# USB_Downloader.net
KiCad netlist of a schematic drawn in Altium Designer
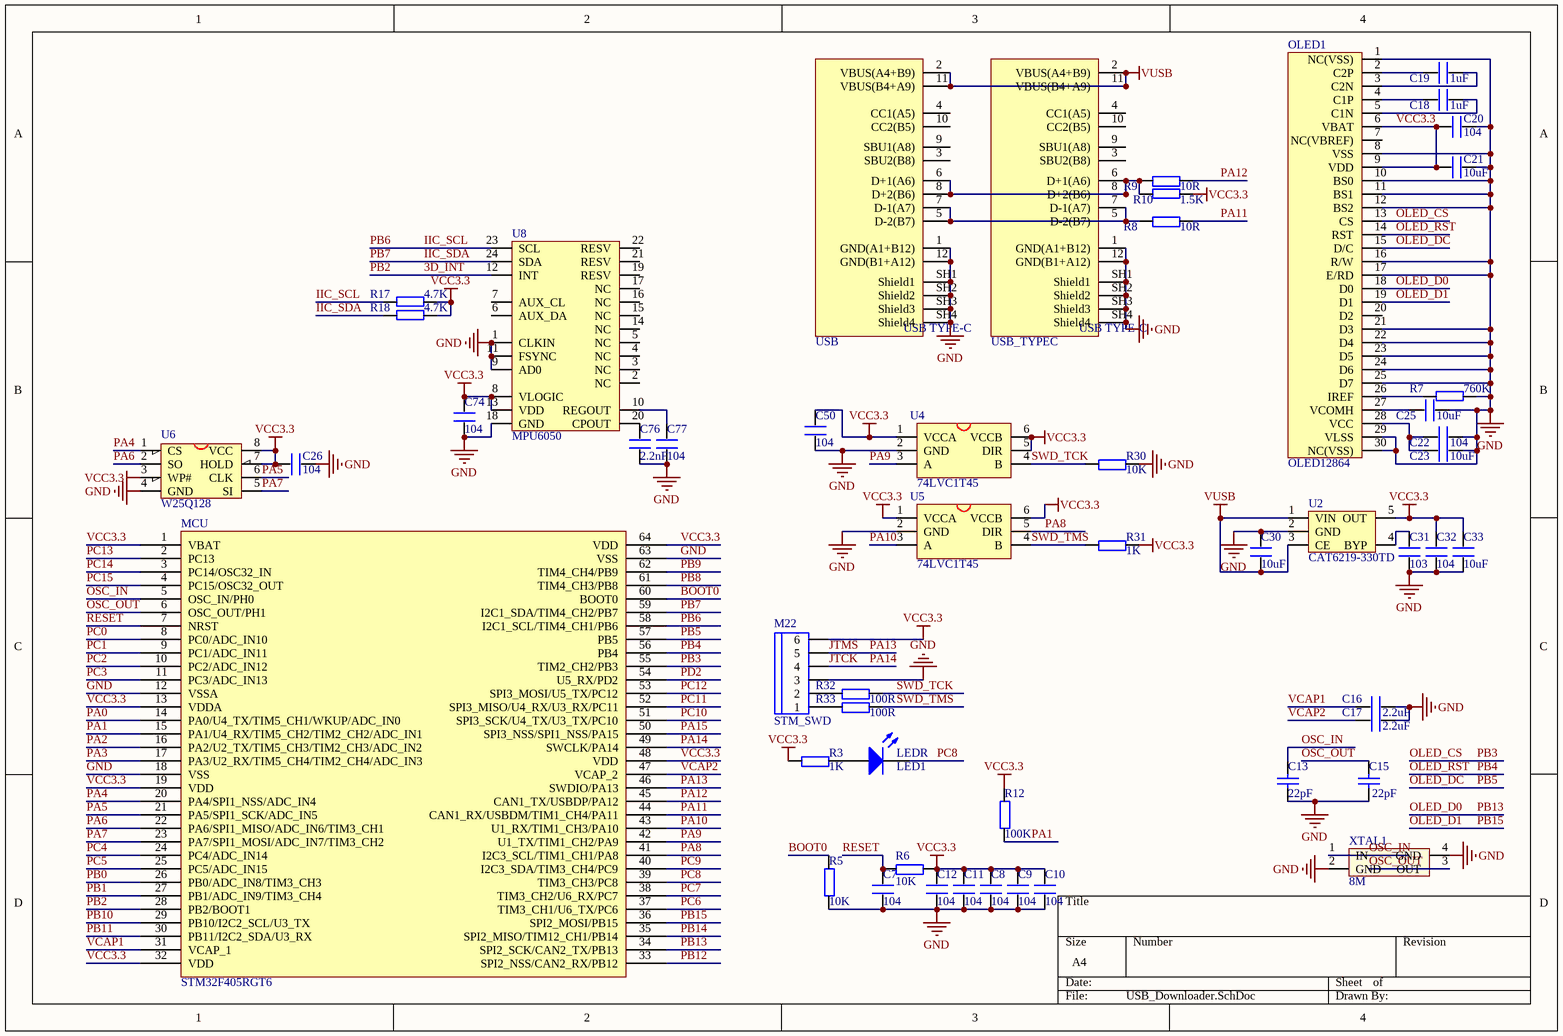
[diagram p0: USB_Downloader.SchDoc]

(export (version "E")
  (design (tool "Eeschema 10.0.6"))
  (components
    (comp (ref "C7")
      (value "104")
      (footprint "C 0603_L")
      (libsource (lib "WarShip V3 STM32103封装库") (part "C"))
    )
    (comp (ref "C8")
      (value "104")
      (footprint "C 0603_L")
      (libsource (lib "WarShip V3 STM32103封装库") (part "C"))
    )
    (comp (ref "C9")
      (value "104")
      (footprint "C 0603_L")
      (libsource (lib "WarShip V3 STM32103封装库") (part "C"))
    )
    (comp (ref "C10")
      (value "104")
      (footprint "C 0603_L")
      (libsource (lib "WarShip V3 STM32103封装库") (part "C"))
    )
    (comp (ref "C11")
      (value "104")
      (footprint "C 0603_L")
      (libsource (lib "WarShip V3 STM32103封装库") (part "C"))
    )
    (comp (ref "C12")
      (value "104")
      (footprint "C 0603_L")
      (libsource (lib "WarShip V3 STM32103封装库") (part "C"))
    )
    (comp (ref "C13") (value "22pF") (footprint "C 0603_L") (libsource (lib "L476") (part "CAP")))
    (comp (ref "C15") (value "22pF") (footprint "C 0603_L") (libsource (lib "L476") (part "CAP")))
    (comp (ref "C16")
      (value "2.2uF")
      (footprint "C 0603_L")
      (libsource (lib "WarShip V3 STM32103封装库") (part "C"))
    )
    (comp (ref "C17")
      (value "2.2uF")
      (footprint "C 0603_L")
      (libsource (lib "WarShip V3 STM32103封装库") (part "C"))
    )
    (comp (ref "C18")
      (value "1uF")
      (footprint "C 0603_L")
      (libsource (lib "WarShip V3 STM32103封装库") (part "C"))
    )
    (comp (ref "C19")
      (value "1uF")
      (footprint "C 0603_L")
      (libsource (lib "WarShip V3 STM32103封装库") (part "C"))
    )
    (comp (ref "C20")
      (value "104")
      (footprint "C 0603_L")
      (libsource (lib "WarShip V3 STM32103封装库") (part "C"))
    )
    (comp (ref "C21")
      (value "10uF")
      (footprint "C 0603_L")
      (libsource (lib "WarShip V3 STM32103封装库") (part "C"))
    )
    (comp (ref "C22")
      (value "104")
      (footprint "C 0603_L")
      (libsource (lib "WarShip V3 STM32103封装库") (part "C"))
    )
    (comp (ref "C23")
      (value "10uF")
      (footprint "C 0603_L")
      (libsource (lib "WarShip V3 STM32103封装库") (part "C"))
    )
    (comp (ref "C25")
      (value "10uF")
      (footprint "C 0603_L")
      (libsource (lib "WarShip V3 STM32103封装库") (part "C"))
    )
    (comp (ref "C26")
      (value "104")
      (footprint "C 0603_L")
      (libsource (lib "WarShip V3 STM32103封装库") (part "C"))
    )
    (comp (ref "C30")
      (value "10uF")
      (footprint "C 0603_L")
      (libsource (lib "WarShip V3 STM32103封装库") (part "C"))
    )
    (comp (ref "C31")
      (value "103")
      (footprint "C 0603_L")
      (libsource (lib "WarShip V3 STM32103封装库") (part "C"))
    )
    (comp (ref "C32")
      (value "104")
      (footprint "C 0603_L")
      (libsource (lib "WarShip V3 STM32103封装库") (part "C"))
    )
    (comp (ref "C33")
      (value "10uF")
      (footprint "C 0603_L")
      (libsource (lib "WarShip V3 STM32103封装库") (part "C"))
    )
    (comp (ref "C50")
      (value "104")
      (footprint "C 0603_L")
      (libsource (lib "WarShip V3 STM32103封装库") (part "C"))
    )
    (comp (ref "C74") (value "104") (footprint "C 0603_L") (libsource (lib "MYCOMLIB") (part "C")))
    (comp (ref "C76") (value "2.2nF") (footprint "C 0603_L") (libsource (lib "MYCOMLIB") (part "C")))
    (comp (ref "C77") (value "104") (footprint "C 0603_L") (libsource (lib "MYCOMLIB") (part "C")))
    (comp (ref "LEDR")
      (value "LED1")
      (footprint "LED 0805B")
      (description "Typical RED, GREEN, YELLOW, AMBER GaAs LED")
      (fields (field (name "PUBLISHER") "Altium Limited"))
      (libsource (lib "阿波罗STM32F4&F7底板封装库") (part "LED2"))
    )
    (comp (ref "M22") (value "STM_SWD") (footprint "SH1.0-6P") (libsource (lib "MiniFly ") (part "HEAD6")))
    (comp (ref "MCU")
      (value "STM32F405RGT6")
      (footprint "LQFP64 10X10_L")
      (description "Flaah:256/RAM:48/IO:51")
      (libsource (lib "ATKF405 V1.1") (part "STM32F405RGT6"))
    )
    (comp (ref "OLED1")
      (value "OLED12864")
      (footprint "OLED_0.96")
      (libsource (lib "OLED模块封装库") (part "OLED12864"))
    )
    (comp (ref "R3")
      (value "1K")
      (footprint "R 0603_L")
      (libsource (lib "WarShip V3 STM32103封装库") (part "R"))
    )
    (comp (ref "R5")
      (value "10K")
      (footprint "R 0603_L")
      (libsource (lib "WarShip V3 STM32103封装库") (part "R"))
    )
    (comp (ref "R6")
      (value "10K")
      (footprint "R 0603_L")
      (libsource (lib "WarShip V3 STM32103封装库") (part "R"))
    )
    (comp (ref "R7")
      (value "760K")
      (footprint "R 0603_L")
      (libsource (lib "WarShip V3 STM32103封装库") (part "R"))
    )
    (comp (ref "R8")
      (value "10R")
      (footprint "R 0603_L")
      (libsource (lib "WarShip V3 STM32103封装库") (part "R"))
    )
    (comp (ref "R9")
      (value "10R")
      (footprint "R 0603_L")
      (libsource (lib "WarShip V3 STM32103封装库") (part "R"))
    )
    (comp (ref "R10")
      (value "1.5K")
      (footprint "R 0603_L")
      (libsource (lib "WarShip V3 STM32103封装库") (part "R"))
    )
    (comp (ref "R12")
      (value "100K")
      (footprint "R 0603_L")
      (libsource (lib "WarShip V3 STM32103封装库") (part "R"))
    )
    (comp (ref "R17")
      (value "4.7K")
      (footprint "R 0603_L")
      (libsource (lib "WarShip V3 STM32103封装库") (part "R"))
    )
    (comp (ref "R18")
      (value "4.7K")
      (footprint "R 0603_L")
      (libsource (lib "WarShip V3 STM32103封装库") (part "R"))
    )
    (comp (ref "R30")
      (value "10K")
      (footprint "R 0603_L")
      (libsource (lib "WarShip V3 STM32103封装库") (part "R"))
    )
    (comp (ref "R31")
      (value "1K")
      (footprint "R 0603_L")
      (libsource (lib "WarShip V3 STM32103封装库") (part "R"))
    )
    (comp (ref "R32")
      (value "100R")
      (footprint "R 0603_L")
      (libsource (lib "WarShip V3 STM32103封装库") (part "R"))
    )
    (comp (ref "R33")
      (value "100R")
      (footprint "R 0603_L")
      (libsource (lib "WarShip V3 STM32103封装库") (part "R"))
    )
    (comp (ref "U2")
      (value "CAT6219-330TD")
      (footprint "SOT23-5L")
      (description "3.3V 500mA LDO")
      (libsource (lib "STM32H743核心板封装库") (part "CAT6219-330TD"))
    )
    (comp (ref "U4")
      (value "74LVC1T45")
      (footprint "SOT363-6L")
      (description "1路双向电平转换")
      (libsource (lib "LovelessingSch") (part "74LVC1T45"))
    )
    (comp (ref "U5")
      (value "74LVC1T45")
      (footprint "SOT363-6L")
      (description "1路双向电平转换")
      (libsource (lib "LovelessingSch") (part "74LVC1T45"))
    )
    (comp (ref "U6")
      (value "W25Q128")
      (footprint "SOP8W_L")
      (description "W25X16;SST25VF016;MX25L1605")
      (libsource (lib "WarShip V3 STM32103封装库") (part "W25X16"))
    )
    (comp (ref "U8")
      (value "MPU6050")
      (footprint "QFN24 4x4_N")
      (description "9轴运动处理传感器")
      (libsource (lib "ALIENTEK_COMPONENT") (part "MPU6050"))
    )
    (comp (ref "USB")
      (value "USB TypeC")
      (footprint "USB Type-C")
      (description "12P TypeC 母座")
      (libsource (lib "ESP32_Weather") (part "USB Type-C"))
    )
    (comp (ref "USB_TYPEC")
      (value "USB TypeC")
      (footprint "USB Type-C")
      (description "12P TypeC 母座")
      (libsource (lib "ESP32_Weather") (part "USB Type-C"))
    )
    (comp (ref "XTAL1")
      (value "8M")
      (footprint "XTAL3225   无源")
      (description "无源贴片晶振")
      (libsource (lib "REMOTOR") (part "XTAL-无源贴片"))
    )
  )
  (nets
    (net (code "1") (name "/3D_INT") (class "Default")
      (node (ref "MCU") (pin "28") (pinfunction "PB2/BOOT1_28") (pintype "passive"))
      (node (ref "U8") (pin "12") (pinfunction "INT_12") (pintype "passive"))
    )
    (net (code "2") (name "/BOOT0") (class "Default")
      (node (ref "MCU") (pin "60") (pinfunction "BOOT0_60") (pintype "passive"))
      (node (ref "R5") (pin "2") (pintype "passive"))
    )
    (net (code "3") (name "/IIC_SCL") (class "Default")
      (node (ref "MCU") (pin "58") (pinfunction "I2C1_SCL/TIM4_CH1/PB6_58") (pintype "passive"))
      (node (ref "R17") (pin "2") (pintype "passive"))
      (node (ref "U8") (pin "23") (pinfunction "SCL_23") (pintype "passive"))
    )
    (net (code "4") (name "/IIC_SDA") (class "Default")
      (node (ref "MCU") (pin "59") (pinfunction "I2C1_SDA/TIM4_CH2/PB7_59") (pintype "passive"))
      (node (ref "R18") (pin "2") (pintype "passive"))
      (node (ref "U8") (pin "24") (pinfunction "SDA_24") (pintype "passive"))
    )
    (net (code "5") (name "/JTCK") (class "Default")
      (node (ref "M22") (pin "4") (pinfunction "4_4") (pintype "passive"))
      (node (ref "MCU") (pin "49") (pinfunction "SWCLK/PA14_49") (pintype "passive"))
    )
    (net (code "6") (name "/JTMS") (class "Default")
      (node (ref "M22") (pin "5") (pinfunction "5_5") (pintype "passive"))
      (node (ref "MCU") (pin "46") (pinfunction "SWDIO/PA13_46") (pintype "passive"))
    )
    (net (code "7") (name "/OLED_CS") (class "Default")
      (node (ref "MCU") (pin "55") (pinfunction "TIM2_CH2/PB3_55") (pintype "passive"))
      (node (ref "OLED1") (pin "13") (pinfunction "CS_13") (pintype "passive"))
    )
    (net (code "8") (name "/OLED_D0") (class "Default")
      (node (ref "MCU") (pin "34") (pinfunction "SPI2_SCK/CAN2_TX/PB13_34") (pintype "passive"))
      (node (ref "OLED1") (pin "18") (pinfunction "D0_18") (pintype "passive"))
    )
    (net (code "9") (name "/OLED_D1") (class "Default")
      (node (ref "MCU") (pin "36") (pinfunction "SPI2_MOSI/PB15_36") (pintype "passive"))
      (node (ref "OLED1") (pin "19") (pinfunction "D1_19") (pintype "passive"))
    )
    (net (code "10") (name "/OLED_DC") (class "Default")
      (node (ref "MCU") (pin "57") (pinfunction "PB5_57") (pintype "passive"))
      (node (ref "OLED1") (pin "15") (pinfunction "D/C_15") (pintype "passive"))
    )
    (net (code "11") (name "/OLED_RST") (class "Default")
      (node (ref "MCU") (pin "56") (pinfunction "PB4_56") (pintype "passive"))
      (node (ref "OLED1") (pin "14") (pinfunction "RST_14") (pintype "passive"))
    )
    (net (code "12") (name "/OSC_IN") (class "Default")
      (node (ref "C13") (pin "2") (pinfunction "2_2") (pintype "passive"))
      (node (ref "MCU") (pin "5") (pinfunction "OSC_IN/PH0_5") (pintype "passive"))
      (node (ref "XTAL1") (pin "1") (pinfunction "IN_1") (pintype "passive"))
    )
    (net (code "13") (name "/OSC_OUT") (class "Default")
      (node (ref "C15") (pin "2") (pinfunction "2_2") (pintype "passive"))
      (node (ref "MCU") (pin "6") (pinfunction "OSC_OUT/PH1_6") (pintype "passive"))
      (node (ref "XTAL1") (pin "3") (pinfunction "OUT_3") (pintype "passive"))
    )
    (net (code "14") (name "/PA0") (class "Default")
      (node (ref "MCU") (pin "14") (pinfunction "PA0/U4_TX/TIM5_CH1/WKUP/ADC_IN0_14") (pintype "passive"))
    )
    (net (code "15") (name "/PA1") (class "Default")
      (node (ref "MCU") (pin "15") (pinfunction "PA1/U4_RX/TIM5_CH2/TIM2_CH2/ADC_IN1_15") (pintype "passive"))
      (node (ref "R12") (pin "1") (pintype "passive"))
    )
    (net (code "16") (name "/PA2") (class "Default")
      (node (ref "MCU") (pin "16") (pinfunction "PA2/U2_TX/TIM5_CH3/TIM2_CH3/ADC_IN2_16") (pintype "passive"))
    )
    (net (code "17") (name "/PA3") (class "Default")
      (node (ref "MCU") (pin "17") (pinfunction "PA3/U2_RX/TIM5_CH4/TIM2_CH4/ADC_IN3_17") (pintype "passive"))
    )
    (net (code "18") (name "/PA4") (class "Default")
      (node (ref "MCU") (pin "20") (pinfunction "PA4/SPI1_NSS/ADC_IN4_20") (pintype "passive"))
      (node (ref "U6") (pin "1") (pinfunction "CS_1") (pintype "passive"))
    )
    (net (code "19") (name "/PA5") (class "Default")
      (node (ref "MCU") (pin "21") (pinfunction "PA5/SPI1_SCK/ADC_IN5_21") (pintype "passive"))
      (node (ref "U6") (pin "6") (pinfunction "CLK_6") (pintype "passive"))
    )
    (net (code "20") (name "/PA6") (class "Default")
      (node (ref "MCU") (pin "22") (pinfunction "PA6/SPI1_MISO/ADC_IN6/TIM3_CH1_22") (pintype "passive"))
      (node (ref "U6") (pin "2") (pinfunction "SO_2") (pintype "passive"))
    )
    (net (code "21") (name "/PA7") (class "Default")
      (node (ref "MCU") (pin "23") (pinfunction "PA7/SPI1_MOSI/ADC_IN7/TIM3_CH2_23") (pintype "passive"))
      (node (ref "U6") (pin "5") (pinfunction "SI_5") (pintype "passive"))
    )
    (net (code "22") (name "/PA8") (class "Default")
      (node (ref "MCU") (pin "41") (pinfunction "I2C3_SCL/TIM1_CH1/PA8_41") (pintype "passive"))
      (node (ref "U5") (pin "5") (pinfunction "DIR_5") (pintype "passive"))
    )
    (net (code "23") (name "/PA9") (class "Default")
      (node (ref "MCU") (pin "42") (pinfunction "U1_TX/TIM1_CH2/PA9_42") (pintype "passive"))
      (node (ref "U4") (pin "3") (pinfunction "A_3") (pintype "passive"))
    )
    (net (code "24") (name "/PA10") (class "Default")
      (node (ref "MCU") (pin "43") (pinfunction "U1_RX/TIM1_CH3/PA10_43") (pintype "passive"))
      (node (ref "U5") (pin "3") (pinfunction "A_3") (pintype "passive"))
    )
    (net (code "25") (name "/PA11") (class "Default")
      (node (ref "MCU") (pin "44") (pinfunction "CAN1_RX/USBDM/TIM1_CH4/PA11_44") (pintype "passive"))
      (node (ref "R8") (pin "2") (pintype "passive"))
    )
    (net (code "26") (name "/PA12") (class "Default")
      (node (ref "MCU") (pin "45") (pinfunction "CAN1_TX/USBDP/PA12_45") (pintype "passive"))
      (node (ref "R9") (pin "2") (pintype "passive"))
    )
    (net (code "27") (name "/PA15") (class "Default")
      (node (ref "MCU") (pin "50") (pinfunction "SPI3_NSS/SPI1_NSS/PA15_50") (pintype "passive"))
    )
    (net (code "28") (name "/PB0") (class "Default")
      (node (ref "MCU") (pin "26") (pinfunction "PB0/ADC_IN8/TIM3_CH3_26") (pintype "passive"))
    )
    (net (code "29") (name "/PB1") (class "Default")
      (node (ref "MCU") (pin "27") (pinfunction "PB1/ADC_IN9/TIM3_CH4_27") (pintype "passive"))
    )
    (net (code "30") (name "/PB8") (class "Default")
      (node (ref "MCU") (pin "61") (pinfunction "TIM4_CH3/PB8_61") (pintype "passive"))
    )
    (net (code "31") (name "/PB9") (class "Default")
      (node (ref "MCU") (pin "62") (pinfunction "TIM4_CH4/PB9_62") (pintype "passive"))
    )
    (net (code "32") (name "/PB10") (class "Default")
      (node (ref "MCU") (pin "29") (pinfunction "PB10/I2C2_SCL/U3_TX_29") (pintype "passive"))
    )
    (net (code "33") (name "/PB11") (class "Default")
      (node (ref "MCU") (pin "30") (pinfunction "PB11/I2C2_SDA/U3_RX_30") (pintype "passive"))
    )
    (net (code "34") (name "/PB12") (class "Default")
      (node (ref "MCU") (pin "33") (pinfunction "SPI2_NSS/CAN2_RX/PB12_33") (pintype "passive"))
    )
    (net (code "35") (name "/PB14") (class "Default")
      (node (ref "MCU") (pin "35") (pinfunction "SPI2_MISO/TIM12_CH1/PB14_35") (pintype "passive"))
    )
    (net (code "36") (name "/PC0") (class "Default")
      (node (ref "MCU") (pin "8") (pinfunction "PC0/ADC_IN10_8") (pintype "passive"))
    )
    (net (code "37") (name "/PC1") (class "Default")
      (node (ref "MCU") (pin "9") (pinfunction "PC1/ADC_IN11_9") (pintype "passive"))
    )
    (net (code "38") (name "/PC2") (class "Default")
      (node (ref "MCU") (pin "10") (pinfunction "PC2/ADC_IN12_10") (pintype "passive"))
    )
    (net (code "39") (name "/PC3") (class "Default")
      (node (ref "MCU") (pin "11") (pinfunction "PC3/ADC_IN13_11") (pintype "passive"))
    )
    (net (code "40") (name "/PC4") (class "Default")
      (node (ref "MCU") (pin "24") (pinfunction "PC4/ADC_IN14_24") (pintype "passive"))
    )
    (net (code "41") (name "/PC5") (class "Default")
      (node (ref "MCU") (pin "25") (pinfunction "PC5/ADC_IN15_25") (pintype "passive"))
    )
    (net (code "42") (name "/PC6") (class "Default")
      (node (ref "MCU") (pin "37") (pinfunction "TIM3_CH1/U6_TX/PC6_37") (pintype "passive"))
    )
    (net (code "43") (name "/PC7") (class "Default")
      (node (ref "MCU") (pin "38") (pinfunction "TIM3_CH2/U6_RX/PC7_38") (pintype "passive"))
    )
    (net (code "44") (name "/PC8") (class "Default")
      (node (ref "LEDR") (pin "2") (pinfunction "K_2") (pintype "passive"))
      (node (ref "MCU") (pin "39") (pinfunction "TIM3_CH3/PC8_39") (pintype "passive"))
    )
    (net (code "45") (name "/PC9") (class "Default")
      (node (ref "MCU") (pin "40") (pinfunction "I2C3_SDA/TIM3_CH4/PC9_40") (pintype "passive"))
    )
    (net (code "46") (name "/PC10") (class "Default")
      (node (ref "MCU") (pin "51") (pinfunction "SPI3_SCK/U4_TX/U3_TX/PC10_51") (pintype "passive"))
    )
    (net (code "47") (name "/PC11") (class "Default")
      (node (ref "MCU") (pin "52") (pinfunction "SPI3_MISO/U4_RX/U3_RX/PC11_52") (pintype "passive"))
    )
    (net (code "48") (name "/PC12") (class "Default")
      (node (ref "MCU") (pin "53") (pinfunction "SPI3_MOSI/U5_TX/PC12_53") (pintype "passive"))
    )
    (net (code "49") (name "/PC13") (class "Default")
      (node (ref "MCU") (pin "2") (pinfunction "PC13_2") (pintype "passive"))
    )
    (net (code "50") (name "/PC14") (class "Default")
      (node (ref "MCU") (pin "3") (pinfunction "PC14/OSC32_IN_3") (pintype "passive"))
    )
    (net (code "51") (name "/PC15") (class "Default")
      (node (ref "MCU") (pin "4") (pinfunction "PC15/OSC32_OUT_4") (pintype "passive"))
    )
    (net (code "52") (name "/PD2") (class "Default")
      (node (ref "MCU") (pin "54") (pinfunction "U5_RX/PD2_54") (pintype "passive"))
    )
    (net (code "53") (name "/RESET") (class "Default")
      (node (ref "C7") (pin "2") (pintype "passive"))
      (node (ref "MCU") (pin "7") (pinfunction "NRST_7") (pintype "passive"))
      (node (ref "R6") (pin "1") (pintype "passive"))
    )
    (net (code "54") (name "/SWD_TCK") (class "Default")
      (node (ref "R30") (pin "1") (pintype "passive"))
      (node (ref "R32") (pin "2") (pintype "passive"))
      (node (ref "U4") (pin "4") (pinfunction "B_4") (pintype "passive"))
    )
    (net (code "55") (name "/SWD_TMS") (class "Default")
      (node (ref "R31") (pin "1") (pintype "passive"))
      (node (ref "R33") (pin "2") (pintype "passive"))
      (node (ref "U5") (pin "4") (pinfunction "B_4") (pintype "passive"))
    )
    (net (code "56") (name "/VCAP1") (class "Default")
      (node (ref "C16") (pin "2") (pintype "passive"))
      (node (ref "MCU") (pin "31") (pinfunction "VCAP_1_31") (pintype "passive"))
    )
    (net (code "57") (name "/VCAP2") (class "Default")
      (node (ref "C17") (pin "2") (pintype "passive"))
      (node (ref "MCU") (pin "47") (pinfunction "VCAP_2_47") (pintype "passive"))
    )
    (net (code "58") (name "GND") (class "Default")
      (node (ref "C10") (pin "1") (pintype "passive"))
      (node (ref "C11") (pin "1") (pintype "passive"))
      (node (ref "C12") (pin "1") (pintype "passive"))
      (node (ref "C13") (pin "1") (pinfunction "1_1") (pintype "passive"))
      (node (ref "C15") (pin "1") (pinfunction "1_1") (pintype "passive"))
      (node (ref "C16") (pin "1") (pintype "passive"))
      (node (ref "C17") (pin "1") (pintype "passive"))
      (node (ref "C20") (pin "1") (pintype "passive"))
      (node (ref "C21") (pin "1") (pintype "passive"))
      (node (ref "C22") (pin "1") (pintype "passive"))
      (node (ref "C23") (pin "1") (pintype "passive"))
      (node (ref "C25") (pin "1") (pintype "passive"))
      (node (ref "C26") (pin "2") (pintype "passive"))
      (node (ref "C30") (pin "2") (pintype "passive"))
      (node (ref "C31") (pin "1") (pintype "passive"))
      (node (ref "C32") (pin "1") (pintype "passive"))
      (node (ref "C33") (pin "1") (pintype "passive"))
      (node (ref "C50") (pin "1") (pintype "passive"))
      (node (ref "C7") (pin "1") (pintype "passive"))
      (node (ref "C74") (pin "1") (pintype "passive"))
      (node (ref "C76") (pin "1") (pintype "passive"))
      (node (ref "C77") (pin "2") (pintype "passive"))
      (node (ref "C8") (pin "1") (pintype "passive"))
      (node (ref "C9") (pin "1") (pintype "passive"))
      (node (ref "M22") (pin "3") (pinfunction "3_3") (pintype "passive"))
      (node (ref "MCU") (pin "12") (pinfunction "VSSA_12") (pintype "passive"))
      (node (ref "MCU") (pin "18") (pinfunction "VSS_18") (pintype "passive"))
      (node (ref "MCU") (pin "63") (pinfunction "VSS_63") (pintype "passive"))
      (node (ref "OLED1") (pin "1") (pinfunction "NC(VSS)_1") (pintype "passive"))
      (node (ref "OLED1") (pin "10") (pinfunction "BS0_10") (pintype "passive"))
      (node (ref "OLED1") (pin "11") (pinfunction "BS1_11") (pintype "passive"))
      (node (ref "OLED1") (pin "12") (pinfunction "BS2_12") (pintype "passive"))
      (node (ref "OLED1") (pin "16") (pinfunction "R/W_16") (pintype "passive"))
      (node (ref "OLED1") (pin "17") (pinfunction "E/RD_17") (pintype "passive"))
      (node (ref "OLED1") (pin "21") (pinfunction "D3_21") (pintype "passive"))
      (node (ref "OLED1") (pin "22") (pinfunction "D4_22") (pintype "passive"))
      (node (ref "OLED1") (pin "23") (pinfunction "D5_23") (pintype "passive"))
      (node (ref "OLED1") (pin "24") (pinfunction "D6_24") (pintype "passive"))
      (node (ref "OLED1") (pin "25") (pinfunction "D7_25") (pintype "passive"))
      (node (ref "OLED1") (pin "29") (pinfunction "VLSS_29") (pintype "passive"))
      (node (ref "OLED1") (pin "30") (pinfunction "NC(VSS)_30") (pintype "passive"))
      (node (ref "OLED1") (pin "8") (pinfunction "VSS_8") (pintype "passive"))
      (node (ref "R30") (pin "2") (pintype "passive"))
      (node (ref "R5") (pin "1") (pintype "passive"))
      (node (ref "R7") (pin "1") (pintype "passive"))
      (node (ref "U2") (pin "2") (pinfunction "GND_2") (pintype "passive"))
      (node (ref "U4") (pin "2") (pinfunction "GND_2") (pintype "passive"))
      (node (ref "U5") (pin "2") (pinfunction "GND_2") (pintype "passive"))
      (node (ref "U6") (pin "4") (pinfunction "GND_4") (pintype "passive"))
      (node (ref "U8") (pin "1") (pinfunction "CLKIN_1") (pintype "passive"))
      (node (ref "U8") (pin "11") (pinfunction "FSYNC_11") (pintype "passive"))
      (node (ref "U8") (pin "18") (pinfunction "GND_18") (pintype "passive"))
      (node (ref "U8") (pin "9") (pinfunction "AD0_9") (pintype "passive"))
      (node (ref "USB") (pin "1") (pinfunction "GND(A1+B12)_1") (pintype "passive"))
      (node (ref "USB") (pin "12") (pinfunction "GND(B1+A12)_12") (pintype "passive"))
      (node (ref "USB") (pin "SH1") (pinfunction "Shield1_SH1") (pintype "passive"))
      (node (ref "USB") (pin "SH2") (pinfunction "Shield2_SH2") (pintype "passive"))
      (node (ref "USB") (pin "SH3") (pinfunction "Shield3_SH3") (pintype "passive"))
      (node (ref "USB") (pin "SH4") (pinfunction "Shield4_SH4") (pintype "passive"))
      (node (ref "USB_TYPEC") (pin "1") (pinfunction "GND(A1+B12)_1") (pintype "passive"))
      (node (ref "USB_TYPEC") (pin "12") (pinfunction "GND(B1+A12)_12") (pintype "passive"))
      (node (ref "USB_TYPEC") (pin "SH1") (pinfunction "Shield1_SH1") (pintype "passive"))
      (node (ref "USB_TYPEC") (pin "SH2") (pinfunction "Shield2_SH2") (pintype "passive"))
      (node (ref "USB_TYPEC") (pin "SH3") (pinfunction "Shield3_SH3") (pintype "passive"))
      (node (ref "USB_TYPEC") (pin "SH4") (pinfunction "Shield4_SH4") (pintype "passive"))
      (node (ref "XTAL1") (pin "2") (pinfunction "GND_2") (pintype "passive"))
      (node (ref "XTAL1") (pin "4") (pinfunction "GND_4") (pintype "passive"))
    )
    (net (code "59") (name "Net-(LEDR-A)") (class "Default")
      (node (ref "LEDR") (pin "1") (pinfunction "A_1") (pintype "passive"))
      (node (ref "R3") (pin "2") (pintype "passive"))
    )
    (net (code "60") (name "Net-(M22-Pad1)") (class "Default")
      (node (ref "M22") (pin "1") (pinfunction "1_1") (pintype "passive"))
      (node (ref "R33") (pin "1") (pintype "passive"))
    )
    (net (code "61") (name "Net-(M22-Pad2)") (class "Default")
      (node (ref "M22") (pin "2") (pinfunction "2_2") (pintype "passive"))
      (node (ref "R32") (pin "1") (pintype "passive"))
    )
    (net (code "62") (name "Net-(OLED1-C1N)") (class "Default")
      (node (ref "C18") (pin "1") (pintype "passive"))
      (node (ref "OLED1") (pin "5") (pinfunction "C1N_5") (pintype "passive"))
    )
    (net (code "63") (name "Net-(OLED1-C1P)") (class "Default")
      (node (ref "C18") (pin "2") (pintype "passive"))
      (node (ref "OLED1") (pin "4") (pinfunction "C1P_4") (pintype "passive"))
    )
    (net (code "64") (name "Net-(OLED1-C2N)") (class "Default")
      (node (ref "C19") (pin "1") (pintype "passive"))
      (node (ref "OLED1") (pin "3") (pinfunction "C2N_3") (pintype "passive"))
    )
    (net (code "65") (name "Net-(OLED1-C2P)") (class "Default")
      (node (ref "C19") (pin "2") (pintype "passive"))
      (node (ref "OLED1") (pin "2") (pinfunction "C2P_2") (pintype "passive"))
    )
    (net (code "66") (name "Net-(OLED1-IREF)") (class "Default")
      (node (ref "OLED1") (pin "26") (pinfunction "IREF_26") (pintype "passive"))
      (node (ref "R7") (pin "2") (pintype "passive"))
    )
    (net (code "67") (name "Net-(OLED1-VCC)") (class "Default")
      (node (ref "C22") (pin "2") (pintype "passive"))
      (node (ref "C23") (pin "2") (pintype "passive"))
      (node (ref "OLED1") (pin "28") (pinfunction "VCC_28") (pintype "passive"))
    )
    (net (code "68") (name "Net-(OLED1-VCOMH)") (class "Default")
      (node (ref "C25") (pin "2") (pintype "passive"))
      (node (ref "OLED1") (pin "27") (pinfunction "VCOMH_27") (pintype "passive"))
    )
    (net (code "69") (name "Net-(U2-BYP)") (class "Default")
      (node (ref "C31") (pin "2") (pintype "passive"))
      (node (ref "U2") (pin "4") (pinfunction "BYP_4") (pintype "passive"))
    )
    (net (code "70") (name "Net-(U8-CPOUT)") (class "Default")
      (node (ref "C76") (pin "2") (pintype "passive"))
      (node (ref "U8") (pin "20") (pinfunction "CPOUT_20") (pintype "passive"))
    )
    (net (code "71") (name "Net-(U8-REGOUT)") (class "Default")
      (node (ref "C77") (pin "1") (pintype "passive"))
      (node (ref "U8") (pin "10") (pinfunction "REGOUT_10") (pintype "passive"))
    )
    (net (code "72") (name "Net-(USB-D+1(A6))") (class "Default")
      (node (ref "R10") (pin "2") (pintype "passive"))
      (node (ref "R9") (pin "1") (pintype "passive"))
      (node (ref "USB") (pin "6") (pinfunction "D+1(A6)_6") (pintype "passive"))
      (node (ref "USB") (pin "8") (pinfunction "D+2(B6)_8") (pintype "passive"))
      (node (ref "USB_TYPEC") (pin "6") (pinfunction "D+1(A6)_6") (pintype "passive"))
      (node (ref "USB_TYPEC") (pin "8") (pinfunction "D+2(B6)_8") (pintype "passive"))
    )
    (net (code "73") (name "Net-(USB-D-1(A7))") (class "Default")
      (node (ref "R8") (pin "1") (pintype "passive"))
      (node (ref "USB") (pin "5") (pinfunction "D-2(B7)_5") (pintype "passive"))
      (node (ref "USB") (pin "7") (pinfunction "D-1(A7)_7") (pintype "passive"))
      (node (ref "USB_TYPEC") (pin "5") (pinfunction "D-2(B7)_5") (pintype "passive"))
      (node (ref "USB_TYPEC") (pin "7") (pinfunction "D-1(A7)_7") (pintype "passive"))
    )
    (net (code "74") (name "VCC3.3") (class "Default")
      (node (ref "C10") (pin "2") (pintype "passive"))
      (node (ref "C11") (pin "2") (pintype "passive"))
      (node (ref "C12") (pin "2") (pintype "passive"))
      (node (ref "C20") (pin "2") (pintype "passive"))
      (node (ref "C21") (pin "2") (pintype "passive"))
      (node (ref "C26") (pin "1") (pintype "passive"))
      (node (ref "C32") (pin "2") (pintype "passive"))
      (node (ref "C33") (pin "2") (pintype "passive"))
      (node (ref "C50") (pin "2") (pintype "passive"))
      (node (ref "C74") (pin "2") (pintype "passive"))
      (node (ref "C8") (pin "2") (pintype "passive"))
      (node (ref "C9") (pin "2") (pintype "passive"))
      (node (ref "M22") (pin "6") (pinfunction "6_6") (pintype "passive"))
      (node (ref "MCU") (pin "1") (pinfunction "VBAT_1") (pintype "passive"))
      (node (ref "MCU") (pin "13") (pinfunction "VDDA_13") (pintype "passive"))
      (node (ref "MCU") (pin "19") (pinfunction "VDD_19") (pintype "passive"))
      (node (ref "MCU") (pin "32") (pinfunction "VDD_32") (pintype "passive"))
      (node (ref "MCU") (pin "48") (pinfunction "VDD_48") (pintype "passive"))
      (node (ref "MCU") (pin "64") (pinfunction "VDD_64") (pintype "passive"))
      (node (ref "OLED1") (pin "6") (pinfunction "VBAT_6") (pintype "passive"))
      (node (ref "OLED1") (pin "9") (pinfunction "VDD_9") (pintype "passive"))
      (node (ref "R10") (pin "1") (pintype "passive"))
      (node (ref "R12") (pin "2") (pintype "passive"))
      (node (ref "R17") (pin "1") (pintype "passive"))
      (node (ref "R18") (pin "1") (pintype "passive"))
      (node (ref "R3") (pin "1") (pintype "passive"))
      (node (ref "R31") (pin "2") (pintype "passive"))
      (node (ref "R6") (pin "2") (pintype "passive"))
      (node (ref "U2") (pin "5") (pinfunction "OUT_5") (pintype "passive"))
      (node (ref "U4") (pin "1") (pinfunction "VCCA_1") (pintype "passive"))
      (node (ref "U4") (pin "5") (pinfunction "DIR_5") (pintype "passive"))
      (node (ref "U4") (pin "6") (pinfunction "VCCB_6") (pintype "passive"))
      (node (ref "U5") (pin "1") (pinfunction "VCCA_1") (pintype "passive"))
      (node (ref "U5") (pin "6") (pinfunction "VCCB_6") (pintype "passive"))
      (node (ref "U6") (pin "3") (pinfunction "WP#_3") (pintype "passive"))
      (node (ref "U6") (pin "7") (pinfunction "HOLD_7") (pintype "passive"))
      (node (ref "U6") (pin "8") (pinfunction "VCC_8") (pintype "passive"))
      (node (ref "U8") (pin "13") (pinfunction "VDD_13") (pintype "passive"))
      (node (ref "U8") (pin "8") (pinfunction "VLOGIC_8") (pintype "passive"))
    )
    (net (code "75") (name "VUSB") (class "Default")
      (node (ref "C30") (pin "1") (pintype "passive"))
      (node (ref "U2") (pin "1") (pinfunction "VIN_1") (pintype "passive"))
      (node (ref "U2") (pin "3") (pinfunction "CE_3") (pintype "passive"))
      (node (ref "USB") (pin "11") (pinfunction "VBUS(B4+A9)_11") (pintype "passive"))
      (node (ref "USB") (pin "2") (pinfunction "VBUS(A4+B9)_2") (pintype "passive"))
      (node (ref "USB_TYPEC") (pin "11") (pinfunction "VBUS(B4+A9)_11") (pintype "passive"))
      (node (ref "USB_TYPEC") (pin "2") (pinfunction "VBUS(A4+B9)_2") (pintype "passive"))
    )
    (net (code "76") (name "unconnected-(OLED1-D2-Pad20)") (class "Default")
      (node (ref "OLED1") (pin "20") (pinfunction "D2_20") (pintype "passive"))
    )
    (net (code "77") (name "unconnected-(OLED1-NC(VBREF)-Pad7)") (class "Default")
      (node (ref "OLED1") (pin "7") (pinfunction "NC(VBREF)_7") (pintype "passive"))
    )
    (net (code "78") (name "unconnected-(U8-AUX_CL-Pad7)") (class "Default")
      (node (ref "U8") (pin "7") (pinfunction "AUX_CL_7") (pintype "passive"))
    )
    (net (code "79") (name "unconnected-(U8-AUX_DA-Pad6)") (class "Default")
      (node (ref "U8") (pin "6") (pinfunction "AUX_DA_6") (pintype "passive"))
    )
    (net (code "80") (name "unconnected-(U8-NC-Pad2)") (class "Default")
      (node (ref "U8") (pin "2") (pinfunction "NC_2") (pintype "passive"))
    )
    (net (code "81") (name "unconnected-(U8-NC-Pad3)") (class "Default")
      (node (ref "U8") (pin "3") (pinfunction "NC_3") (pintype "passive"))
    )
    (net (code "82") (name "unconnected-(U8-NC-Pad4)") (class "Default")
      (node (ref "U8") (pin "4") (pinfunction "NC_4") (pintype "passive"))
    )
    (net (code "83") (name "unconnected-(U8-NC-Pad5)") (class "Default")
      (node (ref "U8") (pin "5") (pinfunction "NC_5") (pintype "passive"))
    )
    (net (code "84") (name "unconnected-(U8-NC-Pad14)") (class "Default")
      (node (ref "U8") (pin "14") (pinfunction "NC_14") (pintype "passive"))
    )
    (net (code "85") (name "unconnected-(U8-NC-Pad15)") (class "Default")
      (node (ref "U8") (pin "15") (pinfunction "NC_15") (pintype "passive"))
    )
    (net (code "86") (name "unconnected-(U8-NC-Pad16)") (class "Default")
      (node (ref "U8") (pin "16") (pinfunction "NC_16") (pintype "passive"))
    )
    (net (code "87") (name "unconnected-(U8-NC-Pad17)") (class "Default")
      (node (ref "U8") (pin "17") (pinfunction "NC_17") (pintype "passive"))
    )
    (net (code "88") (name "unconnected-(U8-RESV-Pad19)") (class "Default")
      (node (ref "U8") (pin "19") (pinfunction "RESV_19") (pintype "passive"))
    )
    (net (code "89") (name "unconnected-(U8-RESV-Pad21)") (class "Default")
      (node (ref "U8") (pin "21") (pinfunction "RESV_21") (pintype "passive"))
    )
    (net (code "90") (name "unconnected-(U8-RESV-Pad22)") (class "Default")
      (node (ref "U8") (pin "22") (pinfunction "RESV_22") (pintype "passive"))
    )
    (net (code "91") (name "unconnected-(USB-CC1(A5)-Pad4)") (class "Default")
      (node (ref "USB") (pin "4") (pinfunction "CC1(A5)_4") (pintype "passive"))
    )
    (net (code "92") (name "unconnected-(USB-CC2(B5)-Pad10)") (class "Default")
      (node (ref "USB") (pin "10") (pinfunction "CC2(B5)_10") (pintype "passive"))
    )
    (net (code "93") (name "unconnected-(USB-SBU1(A8)-Pad9)") (class "Default")
      (node (ref "USB") (pin "9") (pinfunction "SBU1(A8)_9") (pintype "passive"))
    )
    (net (code "94") (name "unconnected-(USB-SBU2(B8)-Pad3)") (class "Default")
      (node (ref "USB") (pin "3") (pinfunction "SBU2(B8)_3") (pintype "passive"))
    )
    (net (code "95") (name "unconnected-(USB_TYPEC-CC1(A5)-Pad4)") (class "Default")
      (node (ref "USB_TYPEC") (pin "4") (pinfunction "CC1(A5)_4") (pintype "passive"))
    )
    (net (code "96") (name "unconnected-(USB_TYPEC-CC2(B5)-Pad10)") (class "Default")
      (node (ref "USB_TYPEC") (pin "10") (pinfunction "CC2(B5)_10") (pintype "passive"))
    )
    (net (code "97") (name "unconnected-(USB_TYPEC-SBU1(A8)-Pad9)") (class "Default")
      (node (ref "USB_TYPEC") (pin "9") (pinfunction "SBU1(A8)_9") (pintype "passive"))
    )
    (net (code "98") (name "unconnected-(USB_TYPEC-SBU2(B8)-Pad3)") (class "Default")
      (node (ref "USB_TYPEC") (pin "3") (pinfunction "SBU2(B8)_3") (pintype "passive"))
    )
  )
)
